# zik-pcb-base-bussed.net
KiCad netlist of a schematic drawn in EAGLE
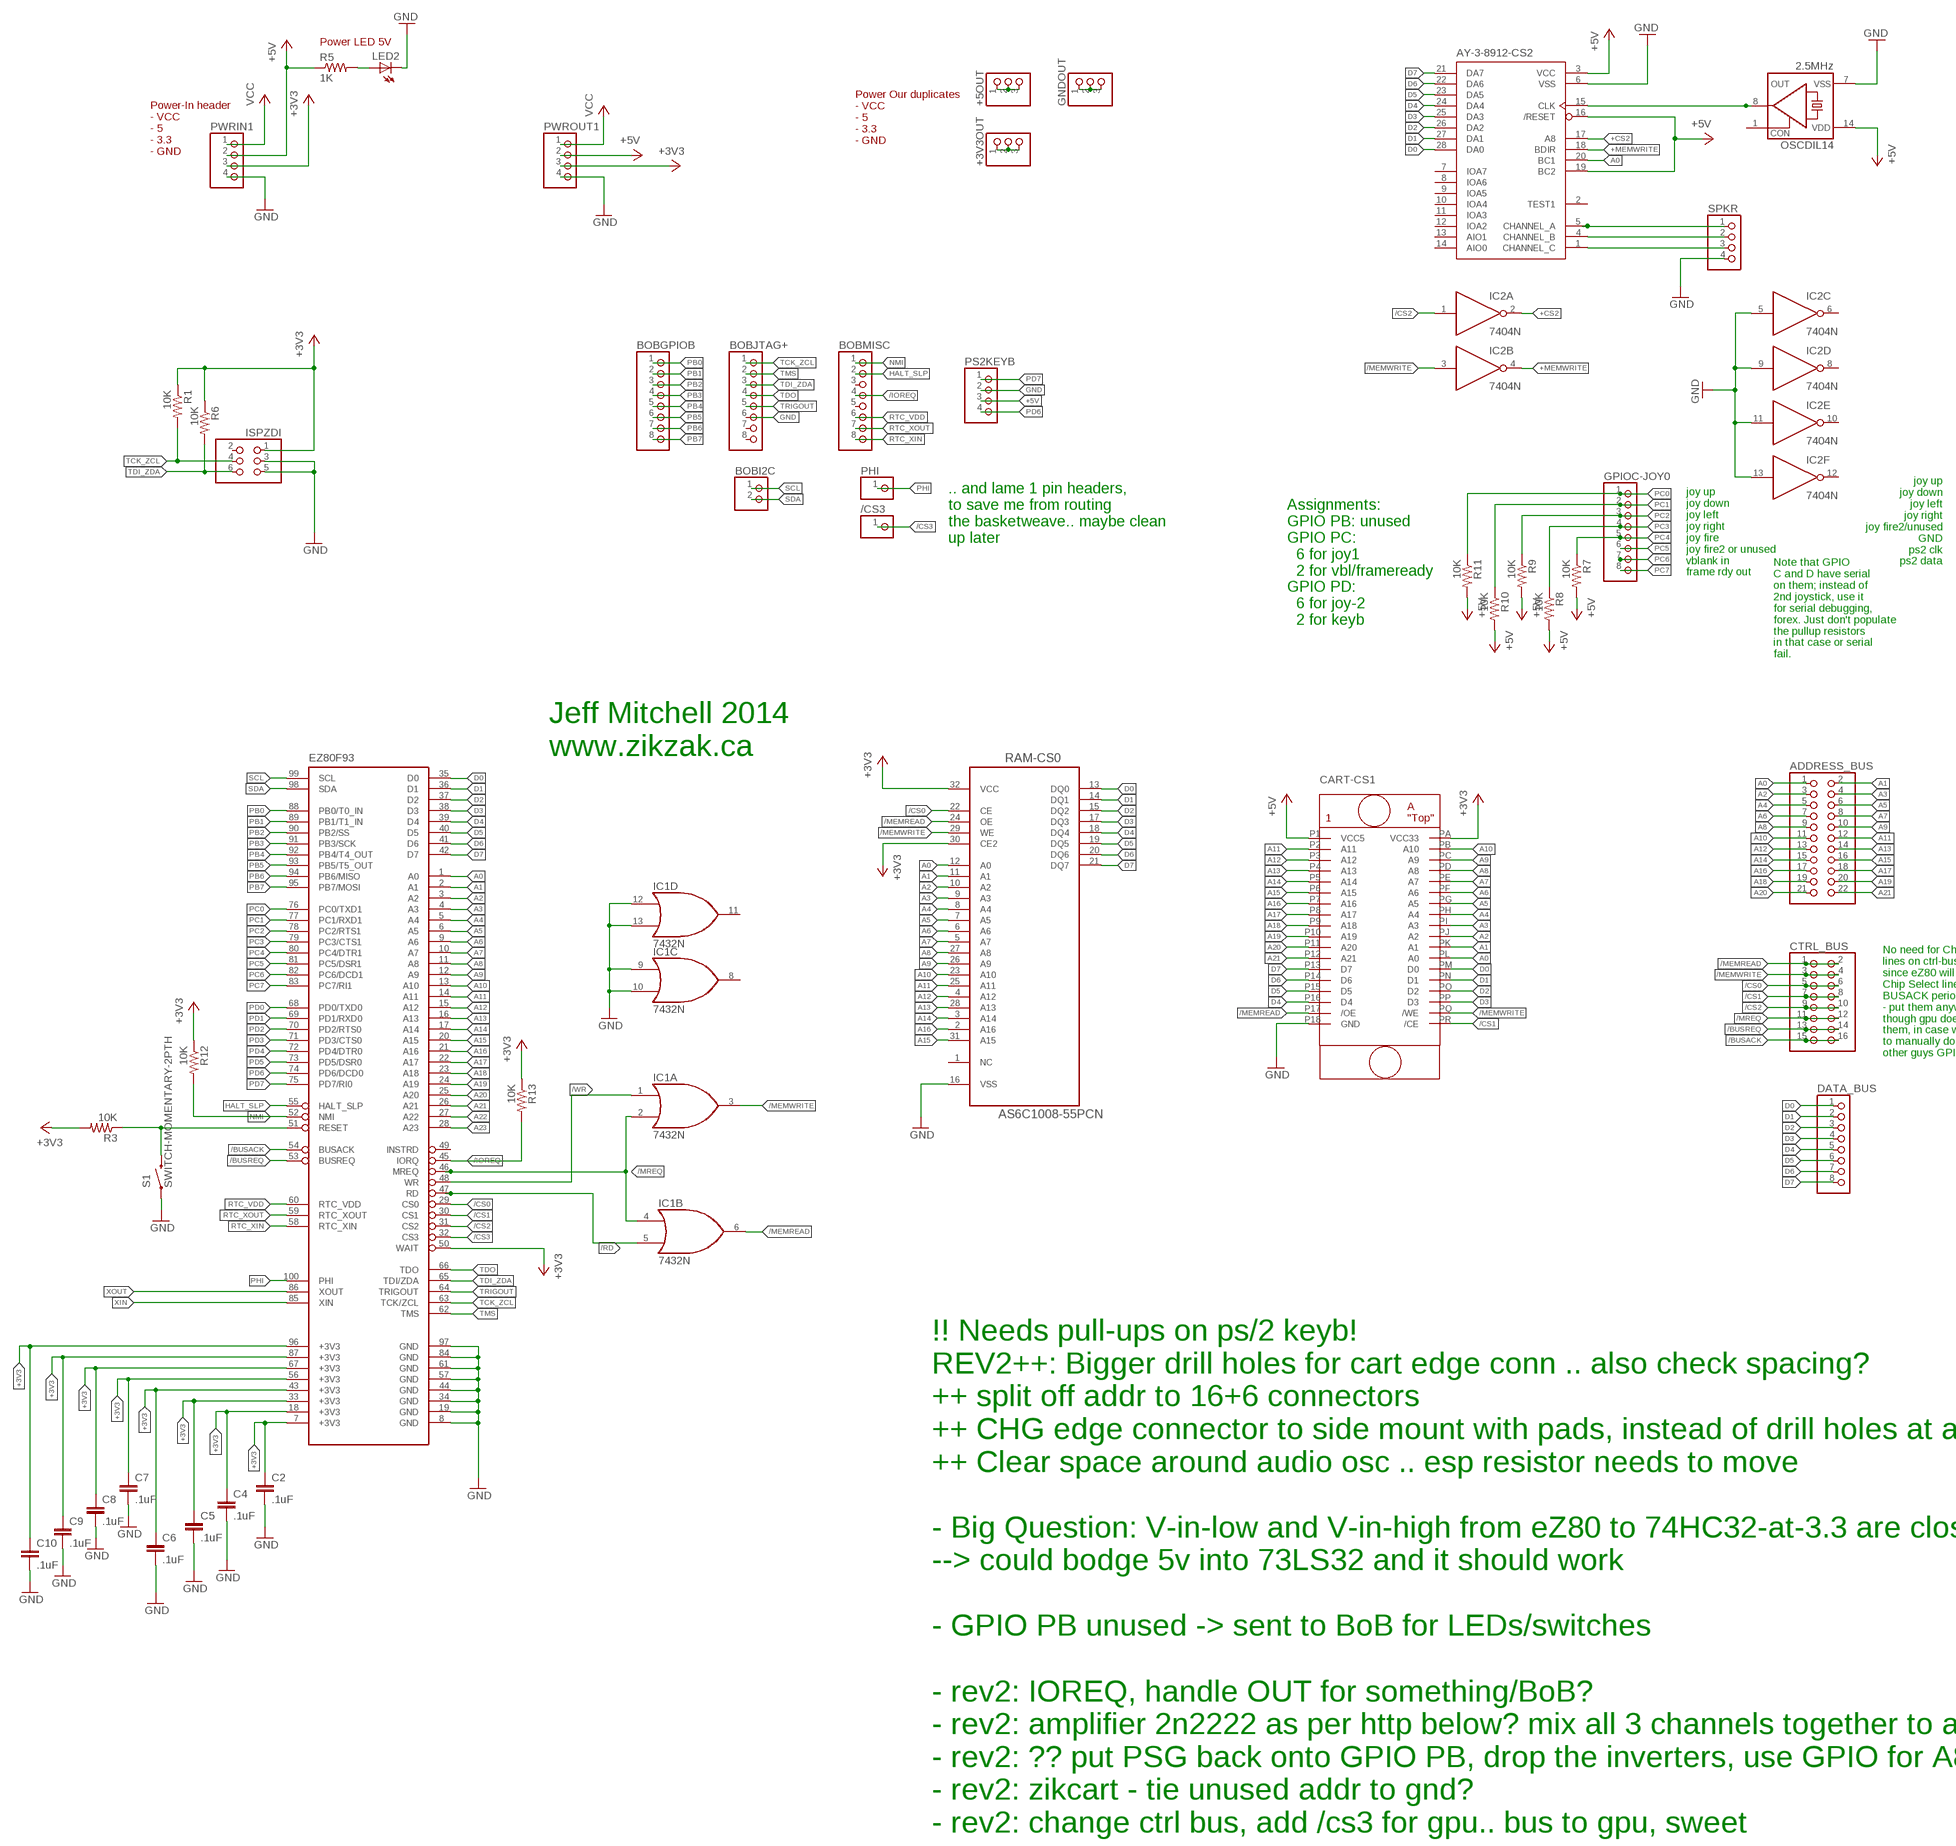
[diagram p0: schematic, sheet 1, part 1 of 2]
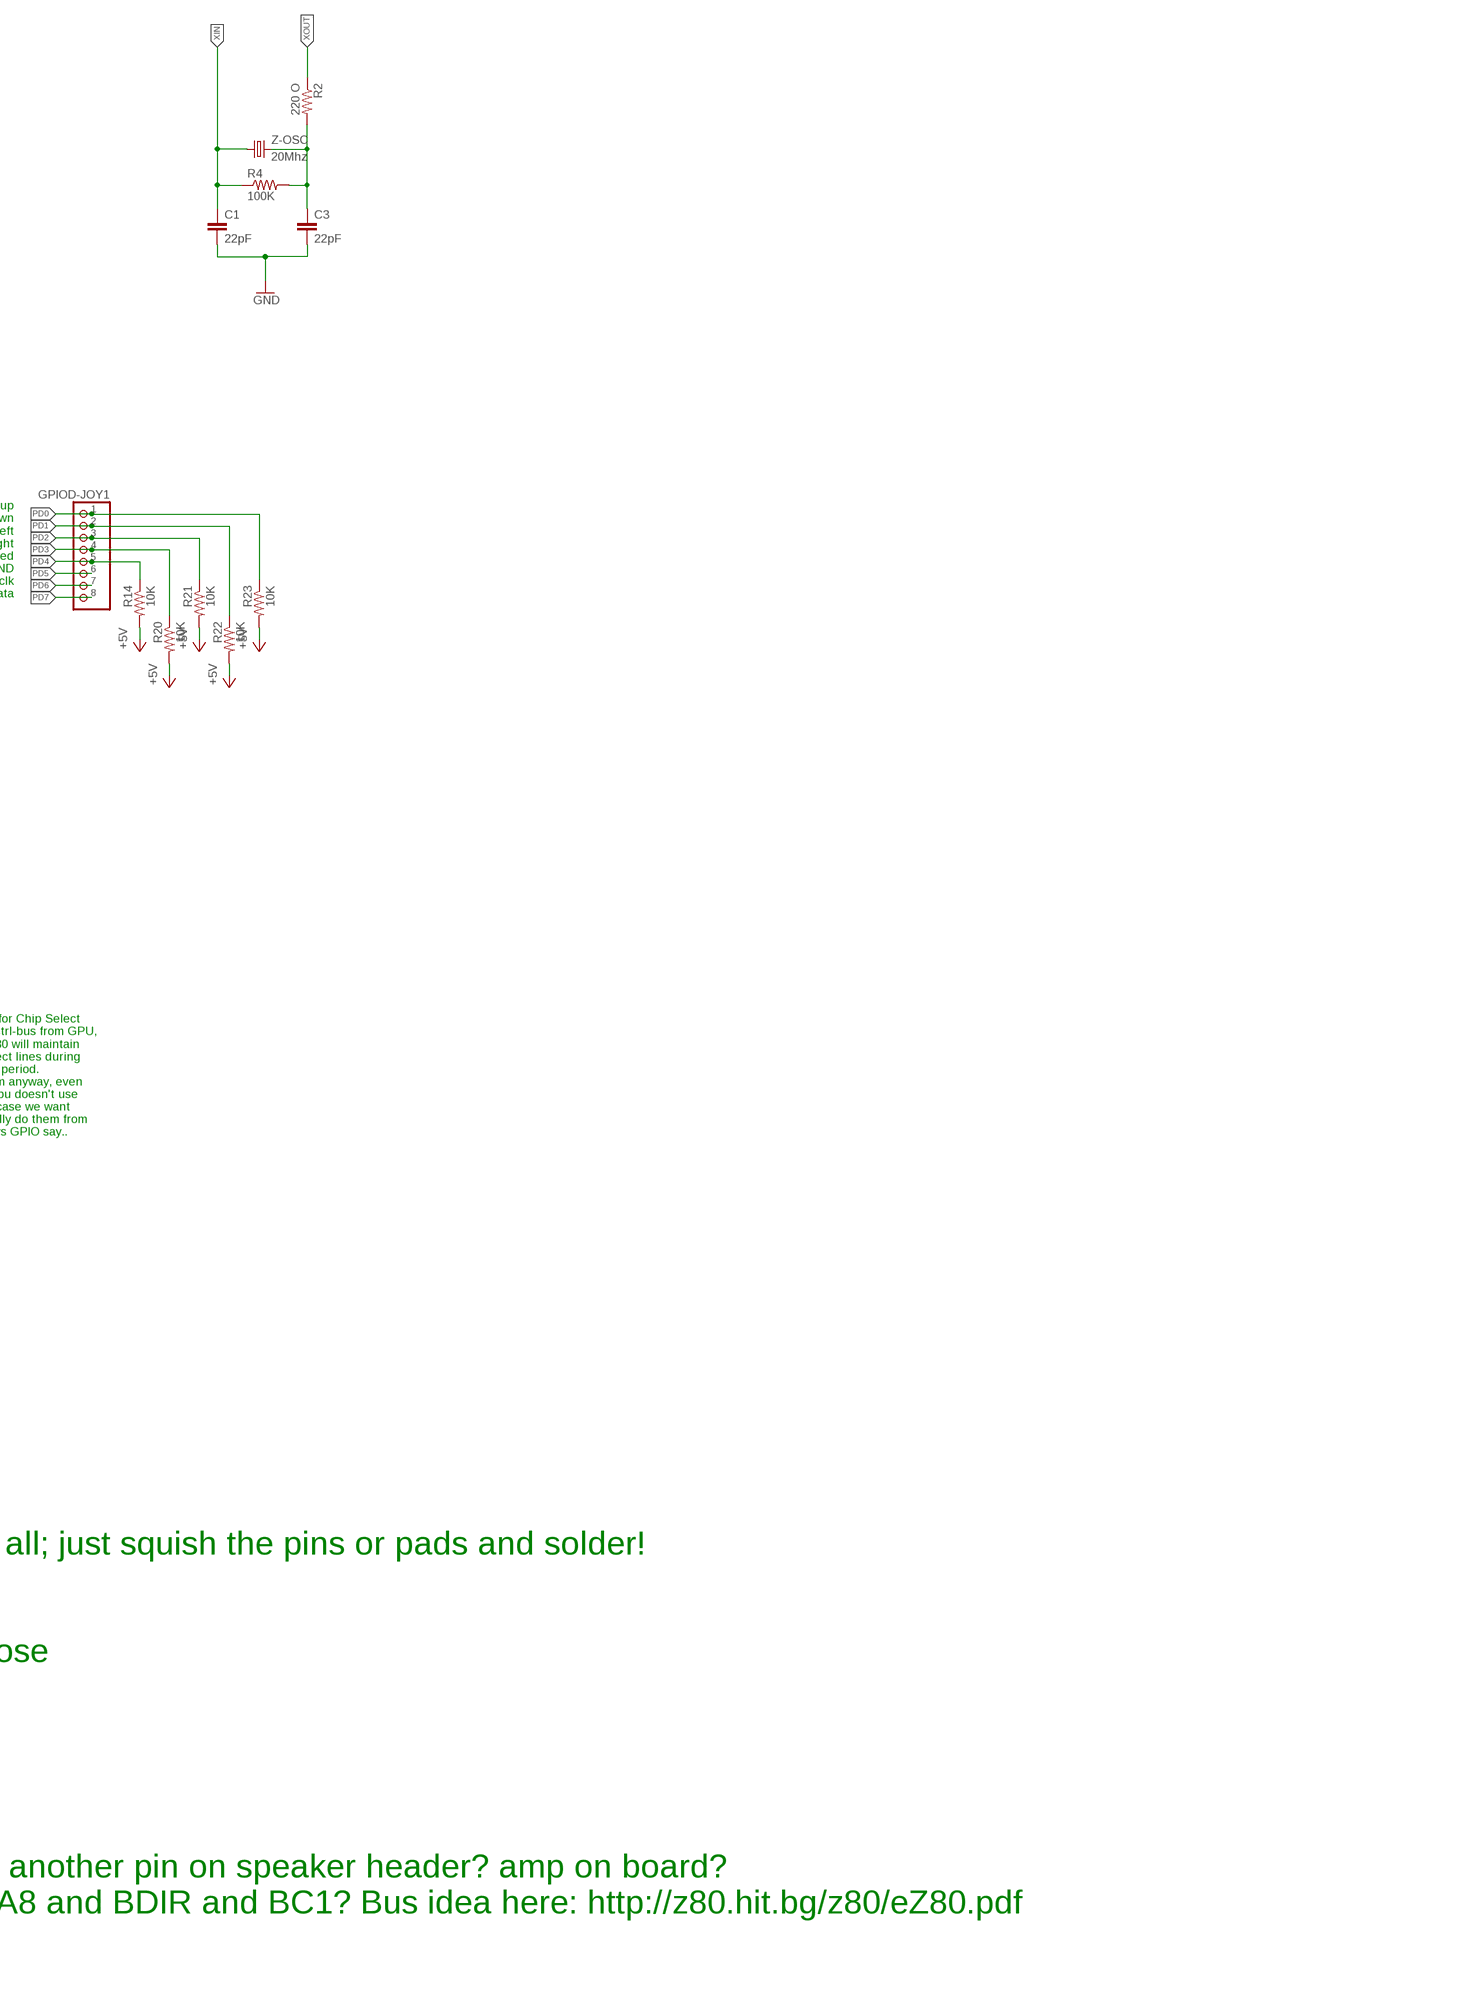
[diagram p1: schematic, sheet 1, part 2 of 2]

(export (version "E")
  (design (tool "Eeschema 10.0.6"))
  (components
    (comp (ref "+3V3OUT")
      (value "PINHD-1X3")
      (footprint "eagle-import:1X03")
      (libsource (lib "eagle-import") (part "PINHD-1X3"))
    )
    (comp (ref "+5OUT")
      (value "PINHD-1X3")
      (footprint "eagle-import:1X03")
      (libsource (lib "eagle-import") (part "PINHD-1X3"))
    )
    (comp (ref "/CS3")
      (value "PINHD-1X1")
      (footprint "eagle-import:1X01")
      (libsource (lib "eagle-import") (part "PINHD-1X1"))
    )
    (comp (ref "ADDRESS_BUS")
      (value "PINHD-2X11")
      (footprint "eagle-import:2X11")
      (libsource (lib "eagle-import") (part "PINHD-2X11"))
    )
    (comp (ref "AY-3-8912-CS2")
      (value "AY-3-8912_28PIN")
      (footprint "eagle-import:DIL28")
      (libsource (lib "eagle-import") (part "AY-3-8912_28PIN"))
    )
    (comp (ref "BOBGPIOB")
      (value "PINHD-1X8")
      (footprint "eagle-import:1X08")
      (libsource (lib "eagle-import") (part "PINHD-1X8"))
    )
    (comp (ref "BOBI2C")
      (value "PINHD-1X2")
      (footprint "eagle-import:1X02")
      (libsource (lib "eagle-import") (part "PINHD-1X2"))
    )
    (comp (ref "BOBJTAG+")
      (value "PINHD-1X8")
      (footprint "eagle-import:1X08")
      (libsource (lib "eagle-import") (part "PINHD-1X8"))
    )
    (comp (ref "BOBMISC")
      (value "PINHD-1X8")
      (footprint "eagle-import:1X08")
      (libsource (lib "eagle-import") (part "PINHD-1X8"))
    )
    (comp (ref "C1")
      (value "22pF")
      (footprint "eagle-import:C025-025X050")
      (libsource (lib "eagle-import") (part "C-EU025-025X050"))
    )
    (comp (ref "C2")
      (value ".1uF")
      (footprint "eagle-import:C025-025X050")
      (libsource (lib "eagle-import") (part "C-EU025-025X050"))
    )
    (comp (ref "C3")
      (value "22pF")
      (footprint "eagle-import:C025-025X050")
      (libsource (lib "eagle-import") (part "C-EU025-025X050"))
    )
    (comp (ref "C4")
      (value ".1uF")
      (footprint "eagle-import:C025-025X050")
      (libsource (lib "eagle-import") (part "C-EU025-025X050"))
    )
    (comp (ref "C5")
      (value ".1uF")
      (footprint "eagle-import:C025-025X050")
      (libsource (lib "eagle-import") (part "C-EU025-025X050"))
    )
    (comp (ref "C6")
      (value ".1uF")
      (footprint "eagle-import:C025-025X050")
      (libsource (lib "eagle-import") (part "C-EU025-025X050"))
    )
    (comp (ref "C7")
      (value ".1uF")
      (footprint "eagle-import:C025-025X050")
      (libsource (lib "eagle-import") (part "C-EU025-025X050"))
    )
    (comp (ref "C8")
      (value ".1uF")
      (footprint "eagle-import:C025-025X050")
      (libsource (lib "eagle-import") (part "C-EU025-025X050"))
    )
    (comp (ref "C9")
      (value ".1uF")
      (footprint "eagle-import:C025-025X050")
      (libsource (lib "eagle-import") (part "C-EU025-025X050"))
    )
    (comp (ref "C10")
      (value ".1uF")
      (footprint "eagle-import:C025-025X050")
      (libsource (lib "eagle-import") (part "C-EU025-025X050"))
    )
    (comp (ref "CART-CS1")
      (value "ZIKCART36")
      (footprint "eagle-import:ZIKCARTSLOT")
      (libsource (lib "eagle-import") (part "ZIKCART36"))
    )
    (comp (ref "CTRL_BUS")
      (value "PINHD-2X8")
      (footprint "eagle-import:2X08")
      (libsource (lib "eagle-import") (part "PINHD-2X8"))
    )
    (comp (ref "DATA_BUS")
      (value "PINHD-1X8")
      (footprint "eagle-import:1X08")
      (libsource (lib "eagle-import") (part "PINHD-1X8"))
    )
    (comp (ref "EZ80F93")
      (value "EZ80F92AZ")
      (footprint "eagle-import:SQFP-S-14X14-100")
      (libsource (lib "eagle-import") (part "EZ80F92AZ"))
    )
    (comp (ref "GNDOUT")
      (value "PINHD-1X3")
      (footprint "eagle-import:1X03")
      (libsource (lib "eagle-import") (part "PINHD-1X3"))
    )
    (comp (ref "GPIOC-JOY0")
      (value "PINHD-1X8")
      (footprint "eagle-import:1X08")
      (libsource (lib "eagle-import") (part "PINHD-1X8"))
    )
    (comp (ref "GPIOD-JOY1")
      (value "PINHD-1X8")
      (footprint "eagle-import:1X08")
      (libsource (lib "eagle-import") (part "PINHD-1X8"))
    )
    (comp (ref "IC1")
      (value "7432N")
      (footprint "eagle-import:DIL14")
      (libsource (lib "eagle-import") (part "7432N"))
    )
    (comp (ref "IC2")
      (value "7404N")
      (footprint "eagle-import:DIL14")
      (libsource (lib "eagle-import") (part "7404N"))
    )
    (comp (ref "ISPZDI")
      (value "PINHD-2X3")
      (footprint "eagle-import:2X03")
      (libsource (lib "eagle-import") (part "PINHD-2X3"))
    )
    (comp (ref "LED2")
      (value "LED5MM")
      (footprint "eagle-import:LED5MM")
      (libsource (lib "eagle-import") (part "LED5MM"))
    )
    (comp (ref "OSCDIL14")
      (value "2.5MHz")
      (footprint "eagle-import:SG51")
      (libsource (lib "eagle-import") (part "CRYSTAL_RES-SG51"))
    )
    (comp (ref "PHI")
      (value "PINHD-1X1")
      (footprint "eagle-import:1X01")
      (libsource (lib "eagle-import") (part "PINHD-1X1"))
    )
    (comp (ref "PS2KEYB")
      (value "PINHD-1X4")
      (footprint "eagle-import:1X04")
      (libsource (lib "eagle-import") (part "PINHD-1X4"))
    )
    (comp (ref "PWRIN1")
      (value "PINHD-1X4")
      (footprint "eagle-import:1X04")
      (libsource (lib "eagle-import") (part "PINHD-1X4"))
    )
    (comp (ref "PWROUT1")
      (value "PINHD-1X4")
      (footprint "eagle-import:1X04")
      (libsource (lib "eagle-import") (part "PINHD-1X4"))
    )
    (comp (ref "R1")
      (value "10K")
      (footprint "eagle-import:0204_7")
      (libsource (lib "eagle-import") (part "R-US_0204/7"))
    )
    (comp (ref "R2")
      (value "220 O")
      (footprint "eagle-import:0204_7")
      (libsource (lib "eagle-import") (part "R-US_0204/7"))
    )
    (comp (ref "R3")
      (value "10K")
      (footprint "eagle-import:0204_7")
      (libsource (lib "eagle-import") (part "R-US_0204/7"))
    )
    (comp (ref "R4")
      (value "100K")
      (footprint "eagle-import:0204_7")
      (libsource (lib "eagle-import") (part "R-US_0204/7"))
    )
    (comp (ref "R5")
      (value "1K")
      (footprint "eagle-import:0207_10")
      (libsource (lib "eagle-import") (part "R-US_0207/10"))
    )
    (comp (ref "R6")
      (value "10K")
      (footprint "eagle-import:0204_7")
      (libsource (lib "eagle-import") (part "R-US_0204/7"))
    )
    (comp (ref "R7")
      (value "10K")
      (footprint "eagle-import:0204_7")
      (libsource (lib "eagle-import") (part "R-US_0204/7"))
    )
    (comp (ref "R8")
      (value "10K")
      (footprint "eagle-import:0204_7")
      (libsource (lib "eagle-import") (part "R-US_0204/7"))
    )
    (comp (ref "R9")
      (value "10K")
      (footprint "eagle-import:0204_7")
      (libsource (lib "eagle-import") (part "R-US_0204/7"))
    )
    (comp (ref "R10")
      (value "10K")
      (footprint "eagle-import:0204_7")
      (libsource (lib "eagle-import") (part "R-US_0204/7"))
    )
    (comp (ref "R11")
      (value "10K")
      (footprint "eagle-import:0204_7")
      (libsource (lib "eagle-import") (part "R-US_0204/7"))
    )
    (comp (ref "R12")
      (value "10K")
      (footprint "eagle-import:0204_7")
      (libsource (lib "eagle-import") (part "R-US_0204/7"))
    )
    (comp (ref "R13")
      (value "10K")
      (footprint "eagle-import:0204_7")
      (libsource (lib "eagle-import") (part "R-US_0204/7"))
    )
    (comp (ref "R14")
      (value "10K")
      (footprint "eagle-import:0204_7")
      (libsource (lib "eagle-import") (part "R-US_0204/7"))
    )
    (comp (ref "R20")
      (value "10K")
      (footprint "eagle-import:0204_7")
      (libsource (lib "eagle-import") (part "R-US_0204/7"))
    )
    (comp (ref "R21")
      (value "10K")
      (footprint "eagle-import:0204_7")
      (libsource (lib "eagle-import") (part "R-US_0204/7"))
    )
    (comp (ref "R22")
      (value "10K")
      (footprint "eagle-import:0204_7")
      (libsource (lib "eagle-import") (part "R-US_0204/7"))
    )
    (comp (ref "R23")
      (value "10K")
      (footprint "eagle-import:0204_7")
      (libsource (lib "eagle-import") (part "R-US_0204/7"))
    )
    (comp (ref "RAM-CS0")
      (value "AS6C1008-55PCN")
      (footprint "eagle-import:DIP254P1524X393-32")
      (libsource (lib "eagle-import") (part "AS6C1008-55PCN"))
    )
    (comp (ref "S1")
      (value "SWITCH-MOMENTARY-2PTH")
      (footprint "eagle-import:TACTILE-PTH")
      (libsource (lib "eagle-import") (part "SWITCH-MOMENTARY-2PTH"))
    )
    (comp (ref "SPKR")
      (value "PINHD-1X4")
      (footprint "eagle-import:1X04")
      (libsource (lib "eagle-import") (part "PINHD-1X4"))
    )
    (comp (ref "Z-OSC")
      (value "20Mhz")
      (footprint "eagle-import:HC49US")
      (libsource (lib "eagle-import") (part "CRYSTALHC49US"))
    )
  )
  (nets
    (net (code "1") (name "+3V3") (class "Default")
      (node (ref "+3V3OUT") (pin "1") (pinfunction "1_1") (pintype "passive"))
      (node (ref "+3V3OUT") (pin "2") (pinfunction "2_2") (pintype "passive"))
      (node (ref "+3V3OUT") (pin "3") (pinfunction "3_3") (pintype "passive"))
      (node (ref "C10") (pin "1") (pinfunction "1_1") (pintype "passive"))
      (node (ref "C2") (pin "1") (pinfunction "1_1") (pintype "passive"))
      (node (ref "C4") (pin "1") (pinfunction "1_1") (pintype "passive"))
      (node (ref "C5") (pin "1") (pinfunction "1_1") (pintype "passive"))
      (node (ref "C6") (pin "1") (pinfunction "1_1") (pintype "passive"))
      (node (ref "C7") (pin "1") (pinfunction "1_1") (pintype "passive"))
      (node (ref "C8") (pin "1") (pinfunction "1_1") (pintype "passive"))
      (node (ref "C9") (pin "1") (pinfunction "1_1") (pintype "passive"))
      (node (ref "CART-CS1") (pin "PA") (pinfunction "VCC33_PA") (pintype "bidirectional"))
      (node (ref "EZ80F93") (pin "18") (pinfunction "+3V3_18") (pintype "power_in"))
      (node (ref "EZ80F93") (pin "33") (pinfunction "+3V3_33") (pintype "power_in"))
      (node (ref "EZ80F93") (pin "43") (pinfunction "+3V3_43") (pintype "power_in"))
      (node (ref "EZ80F93") (pin "50") (pinfunction "WAIT_50") (pintype "input"))
      (node (ref "EZ80F93") (pin "56") (pinfunction "+3V3_56") (pintype "power_in"))
      (node (ref "EZ80F93") (pin "67") (pinfunction "+3V3_67") (pintype "power_in"))
      (node (ref "EZ80F93") (pin "7") (pinfunction "+3V3_7") (pintype "power_in"))
      (node (ref "EZ80F93") (pin "87") (pinfunction "+3V3_87") (pintype "power_in"))
      (node (ref "EZ80F93") (pin "96") (pinfunction "+3V3_96") (pintype "power_in"))
      (node (ref "ISPZDI") (pin "1") (pinfunction "1_1") (pintype "passive"))
      (node (ref "PWRIN1") (pin "3") (pinfunction "3_3") (pintype "passive"))
      (node (ref "PWROUT1") (pin "3") (pinfunction "3_3") (pintype "passive"))
      (node (ref "R1") (pin "1") (pinfunction "1_1") (pintype "passive"))
      (node (ref "R12") (pin "1") (pinfunction "1_1") (pintype "passive"))
      (node (ref "R13") (pin "1") (pinfunction "1_1") (pintype "passive"))
      (node (ref "R3") (pin "2") (pinfunction "2_2") (pintype "passive"))
      (node (ref "R6") (pin "1") (pinfunction "1_1") (pintype "passive"))
      (node (ref "RAM-CS0") (pin "30") (pinfunction "CE2_30") (pintype "input"))
      (node (ref "RAM-CS0") (pin "32") (pinfunction "VCC_32") (pintype "power_in"))
    )
    (net (code "2") (name "+5V") (class "Default")
      (node (ref "+5OUT") (pin "1") (pinfunction "1_1") (pintype "passive"))
      (node (ref "+5OUT") (pin "2") (pinfunction "2_2") (pintype "passive"))
      (node (ref "+5OUT") (pin "3") (pinfunction "3_3") (pintype "passive"))
      (node (ref "AY-3-8912-CS2") (pin "16") (pinfunction "/RESET_16") (pintype "input"))
      (node (ref "AY-3-8912-CS2") (pin "19") (pinfunction "BC2_19") (pintype "input"))
      (node (ref "AY-3-8912-CS2") (pin "3") (pinfunction "VCC_3") (pintype "power_in"))
      (node (ref "CART-CS1") (pin "P1") (pinfunction "VCC5_P1") (pintype "bidirectional"))
      (node (ref "OSCDIL14") (pin "14") (pinfunction "VDD_14") (pintype "power_in"))
      (node (ref "PS2KEYB") (pin "3") (pinfunction "3_3") (pintype "passive"))
      (node (ref "PWRIN1") (pin "2") (pinfunction "2_2") (pintype "passive"))
      (node (ref "PWROUT1") (pin "2") (pinfunction "2_2") (pintype "passive"))
      (node (ref "R10") (pin "2") (pinfunction "2_2") (pintype "passive"))
      (node (ref "R11") (pin "2") (pinfunction "2_2") (pintype "passive"))
      (node (ref "R14") (pin "2") (pinfunction "2_2") (pintype "passive"))
      (node (ref "R20") (pin "2") (pinfunction "2_2") (pintype "passive"))
      (node (ref "R21") (pin "2") (pinfunction "2_2") (pintype "passive"))
      (node (ref "R22") (pin "2") (pinfunction "2_2") (pintype "passive"))
      (node (ref "R23") (pin "2") (pinfunction "2_2") (pintype "passive"))
      (node (ref "R5") (pin "1") (pinfunction "1_1") (pintype "passive"))
      (node (ref "R7") (pin "2") (pinfunction "2_2") (pintype "passive"))
      (node (ref "R8") (pin "2") (pinfunction "2_2") (pintype "passive"))
      (node (ref "R9") (pin "2") (pinfunction "2_2") (pintype "passive"))
    )
    (net (code "3") (name "+CS2") (class "Default")
      (node (ref "AY-3-8912-CS2") (pin "17") (pinfunction "A8_17") (pintype "input"))
      (node (ref "IC2") (pin "2") (pinfunction "O_2") (pintype "output"))
    )
    (net (code "4") (name "+MEMWRITE") (class "Default")
      (node (ref "AY-3-8912-CS2") (pin "18") (pinfunction "BDIR_18") (pintype "input"))
      (node (ref "IC2") (pin "4") (pinfunction "O_4") (pintype "output"))
    )
    (net (code "5") (name "A0") (class "Default")
      (node (ref "ADDRESS_BUS") (pin "1") (pinfunction "1_1") (pintype "passive"))
      (node (ref "AY-3-8912-CS2") (pin "20") (pinfunction "BC1_20") (pintype "input"))
      (node (ref "CART-CS1") (pin "PL") (pinfunction "A0_PL") (pintype "bidirectional"))
      (node (ref "EZ80F93") (pin "1") (pinfunction "A0_1") (pintype "bidirectional"))
      (node (ref "RAM-CS0") (pin "12") (pinfunction "A0_12") (pintype "input"))
    )
    (net (code "6") (name "A1") (class "Default")
      (node (ref "ADDRESS_BUS") (pin "2") (pinfunction "2_2") (pintype "passive"))
      (node (ref "CART-CS1") (pin "PK") (pinfunction "A1_PK") (pintype "bidirectional"))
      (node (ref "EZ80F93") (pin "2") (pinfunction "A1_2") (pintype "bidirectional"))
      (node (ref "RAM-CS0") (pin "11") (pinfunction "A1_11") (pintype "input"))
    )
    (net (code "7") (name "A2") (class "Default")
      (node (ref "ADDRESS_BUS") (pin "3") (pinfunction "3_3") (pintype "passive"))
      (node (ref "CART-CS1") (pin "PJ") (pinfunction "A2_PJ") (pintype "bidirectional"))
      (node (ref "EZ80F93") (pin "3") (pinfunction "A2_3") (pintype "bidirectional"))
      (node (ref "RAM-CS0") (pin "10") (pinfunction "A2_10") (pintype "input"))
    )
    (net (code "8") (name "A3") (class "Default")
      (node (ref "ADDRESS_BUS") (pin "4") (pinfunction "4_4") (pintype "passive"))
      (node (ref "CART-CS1") (pin "PI") (pinfunction "A3_PI") (pintype "bidirectional"))
      (node (ref "EZ80F93") (pin "4") (pinfunction "A3_4") (pintype "bidirectional"))
      (node (ref "RAM-CS0") (pin "9") (pinfunction "A3_9") (pintype "input"))
    )
    (net (code "9") (name "A4") (class "Default")
      (node (ref "ADDRESS_BUS") (pin "5") (pinfunction "5_5") (pintype "passive"))
      (node (ref "CART-CS1") (pin "PH") (pinfunction "A4_PH") (pintype "bidirectional"))
      (node (ref "EZ80F93") (pin "5") (pinfunction "A4_5") (pintype "bidirectional"))
      (node (ref "RAM-CS0") (pin "8") (pinfunction "A4_8") (pintype "input"))
    )
    (net (code "10") (name "A5") (class "Default")
      (node (ref "ADDRESS_BUS") (pin "6") (pinfunction "6_6") (pintype "passive"))
      (node (ref "CART-CS1") (pin "PG") (pinfunction "A5_PG") (pintype "bidirectional"))
      (node (ref "EZ80F93") (pin "6") (pinfunction "A5_6") (pintype "bidirectional"))
      (node (ref "RAM-CS0") (pin "7") (pinfunction "A5_7") (pintype "input"))
    )
    (net (code "11") (name "A6") (class "Default")
      (node (ref "ADDRESS_BUS") (pin "7") (pinfunction "7_7") (pintype "passive"))
      (node (ref "CART-CS1") (pin "PF") (pinfunction "A6_PF") (pintype "bidirectional"))
      (node (ref "EZ80F93") (pin "9") (pinfunction "A6_9") (pintype "bidirectional"))
      (node (ref "RAM-CS0") (pin "6") (pinfunction "A6_6") (pintype "input"))
    )
    (net (code "12") (name "A7") (class "Default")
      (node (ref "ADDRESS_BUS") (pin "8") (pinfunction "8_8") (pintype "passive"))
      (node (ref "CART-CS1") (pin "PE") (pinfunction "A7_PE") (pintype "bidirectional"))
      (node (ref "EZ80F93") (pin "10") (pinfunction "A7_10") (pintype "bidirectional"))
      (node (ref "RAM-CS0") (pin "5") (pinfunction "A7_5") (pintype "input"))
    )
    (net (code "13") (name "A8") (class "Default")
      (node (ref "ADDRESS_BUS") (pin "9") (pinfunction "9_9") (pintype "passive"))
      (node (ref "CART-CS1") (pin "PD") (pinfunction "A8_PD") (pintype "bidirectional"))
      (node (ref "EZ80F93") (pin "11") (pinfunction "A8_11") (pintype "bidirectional"))
      (node (ref "RAM-CS0") (pin "27") (pinfunction "A8_27") (pintype "input"))
    )
    (net (code "14") (name "A9") (class "Default")
      (node (ref "ADDRESS_BUS") (pin "10") (pinfunction "10_10") (pintype "passive"))
      (node (ref "CART-CS1") (pin "PC") (pinfunction "A9_PC") (pintype "bidirectional"))
      (node (ref "EZ80F93") (pin "12") (pinfunction "A9_12") (pintype "bidirectional"))
      (node (ref "RAM-CS0") (pin "26") (pinfunction "A9_26") (pintype "input"))
    )
    (net (code "15") (name "A10") (class "Default")
      (node (ref "ADDRESS_BUS") (pin "11") (pinfunction "11_11") (pintype "passive"))
      (node (ref "CART-CS1") (pin "PB") (pinfunction "A10_PB") (pintype "bidirectional"))
      (node (ref "EZ80F93") (pin "13") (pinfunction "A10_13") (pintype "bidirectional"))
      (node (ref "RAM-CS0") (pin "23") (pinfunction "A10_23") (pintype "input"))
    )
    (net (code "16") (name "A11") (class "Default")
      (node (ref "ADDRESS_BUS") (pin "12") (pinfunction "12_12") (pintype "passive"))
      (node (ref "CART-CS1") (pin "P2") (pinfunction "A11_P2") (pintype "bidirectional"))
      (node (ref "EZ80F93") (pin "14") (pinfunction "A11_14") (pintype "bidirectional"))
      (node (ref "RAM-CS0") (pin "25") (pinfunction "A11_25") (pintype "input"))
    )
    (net (code "17") (name "A12") (class "Default")
      (node (ref "ADDRESS_BUS") (pin "13") (pinfunction "13_13") (pintype "passive"))
      (node (ref "CART-CS1") (pin "P3") (pinfunction "A12_P3") (pintype "bidirectional"))
      (node (ref "EZ80F93") (pin "15") (pinfunction "A12_15") (pintype "bidirectional"))
      (node (ref "RAM-CS0") (pin "4") (pinfunction "A12_4") (pintype "input"))
    )
    (net (code "18") (name "A13") (class "Default")
      (node (ref "ADDRESS_BUS") (pin "14") (pinfunction "14_14") (pintype "passive"))
      (node (ref "CART-CS1") (pin "P4") (pinfunction "A13_P4") (pintype "bidirectional"))
      (node (ref "EZ80F93") (pin "16") (pinfunction "A13_16") (pintype "bidirectional"))
      (node (ref "RAM-CS0") (pin "28") (pinfunction "A13_28") (pintype "input"))
    )
    (net (code "19") (name "A14") (class "Default")
      (node (ref "ADDRESS_BUS") (pin "15") (pinfunction "15_15") (pintype "passive"))
      (node (ref "CART-CS1") (pin "P5") (pinfunction "A14_P5") (pintype "bidirectional"))
      (node (ref "EZ80F93") (pin "17") (pinfunction "A14_17") (pintype "bidirectional"))
      (node (ref "RAM-CS0") (pin "3") (pinfunction "A14_3") (pintype "input"))
    )
    (net (code "20") (name "A15") (class "Default")
      (node (ref "ADDRESS_BUS") (pin "16") (pinfunction "16_16") (pintype "passive"))
      (node (ref "CART-CS1") (pin "P6") (pinfunction "A15_P6") (pintype "bidirectional"))
      (node (ref "EZ80F93") (pin "20") (pinfunction "A15_20") (pintype "bidirectional"))
      (node (ref "RAM-CS0") (pin "31") (pinfunction "A15_31") (pintype "input"))
    )
    (net (code "21") (name "A16") (class "Default")
      (node (ref "ADDRESS_BUS") (pin "17") (pinfunction "17_17") (pintype "passive"))
      (node (ref "CART-CS1") (pin "P7") (pinfunction "A16_P7") (pintype "bidirectional"))
      (node (ref "EZ80F93") (pin "21") (pinfunction "A16_21") (pintype "bidirectional"))
      (node (ref "RAM-CS0") (pin "2") (pinfunction "A16_2") (pintype "input"))
    )
    (net (code "22") (name "A17") (class "Default")
      (node (ref "ADDRESS_BUS") (pin "18") (pinfunction "18_18") (pintype "passive"))
      (node (ref "CART-CS1") (pin "P8") (pinfunction "A17_P8") (pintype "bidirectional"))
      (node (ref "EZ80F93") (pin "22") (pinfunction "A17_22") (pintype "bidirectional"))
    )
    (net (code "23") (name "A18") (class "Default")
      (node (ref "ADDRESS_BUS") (pin "19") (pinfunction "19_19") (pintype "passive"))
      (node (ref "CART-CS1") (pin "P9") (pinfunction "A18_P9") (pintype "bidirectional"))
      (node (ref "EZ80F93") (pin "23") (pinfunction "A18_23") (pintype "bidirectional"))
    )
    (net (code "24") (name "A19") (class "Default")
      (node (ref "ADDRESS_BUS") (pin "20") (pinfunction "20_20") (pintype "passive"))
      (node (ref "CART-CS1") (pin "P10") (pinfunction "A19_P10") (pintype "bidirectional"))
      (node (ref "EZ80F93") (pin "24") (pinfunction "A19_24") (pintype "bidirectional"))
    )
    (net (code "25") (name "A20") (class "Default")
      (node (ref "ADDRESS_BUS") (pin "21") (pinfunction "21_21") (pintype "passive"))
      (node (ref "CART-CS1") (pin "P11") (pinfunction "A20_P11") (pintype "bidirectional"))
      (node (ref "EZ80F93") (pin "25") (pinfunction "A20_25") (pintype "bidirectional"))
    )
    (net (code "26") (name "A21") (class "Default")
      (node (ref "ADDRESS_BUS") (pin "22") (pinfunction "22_22") (pintype "passive"))
      (node (ref "CART-CS1") (pin "P12") (pinfunction "A21_P12") (pintype "bidirectional"))
      (node (ref "EZ80F93") (pin "26") (pinfunction "A21_26") (pintype "bidirectional"))
    )
    (net (code "27") (name "A22") (class "Default")
      (node (ref "EZ80F93") (pin "27") (pinfunction "A22_27") (pintype "bidirectional"))
    )
    (net (code "28") (name "A23") (class "Default")
      (node (ref "EZ80F93") (pin "28") (pinfunction "A23_28") (pintype "bidirectional"))
    )
    (net (code "29") (name "D0") (class "Default")
      (node (ref "AY-3-8912-CS2") (pin "28") (pinfunction "DA0_28") (pintype "bidirectional"))
      (node (ref "CART-CS1") (pin "PM") (pinfunction "D0_PM") (pintype "bidirectional"))
      (node (ref "DATA_BUS") (pin "1") (pinfunction "1_1") (pintype "passive"))
      (node (ref "EZ80F93") (pin "35") (pinfunction "D0_35") (pintype "bidirectional"))
      (node (ref "RAM-CS0") (pin "13") (pinfunction "DQ0_13") (pintype "bidirectional"))
    )
    (net (code "30") (name "D1") (class "Default")
      (node (ref "AY-3-8912-CS2") (pin "27") (pinfunction "DA1_27") (pintype "bidirectional"))
      (node (ref "CART-CS1") (pin "PN") (pinfunction "D1_PN") (pintype "bidirectional"))
      (node (ref "DATA_BUS") (pin "2") (pinfunction "2_2") (pintype "passive"))
      (node (ref "EZ80F93") (pin "36") (pinfunction "D1_36") (pintype "bidirectional"))
      (node (ref "RAM-CS0") (pin "14") (pinfunction "DQ1_14") (pintype "bidirectional"))
    )
    (net (code "31") (name "D2") (class "Default")
      (node (ref "AY-3-8912-CS2") (pin "26") (pinfunction "DA2_26") (pintype "bidirectional"))
      (node (ref "CART-CS1") (pin "PO") (pinfunction "D2_PO") (pintype "bidirectional"))
      (node (ref "DATA_BUS") (pin "3") (pinfunction "3_3") (pintype "passive"))
      (node (ref "EZ80F93") (pin "37") (pinfunction "D2_37") (pintype "bidirectional"))
      (node (ref "RAM-CS0") (pin "15") (pinfunction "DQ2_15") (pintype "bidirectional"))
    )
    (net (code "32") (name "D3") (class "Default")
      (node (ref "AY-3-8912-CS2") (pin "25") (pinfunction "DA3_25") (pintype "bidirectional"))
      (node (ref "CART-CS1") (pin "PP") (pinfunction "D3_PP") (pintype "bidirectional"))
      (node (ref "DATA_BUS") (pin "4") (pinfunction "4_4") (pintype "passive"))
      (node (ref "EZ80F93") (pin "38") (pinfunction "D3_38") (pintype "bidirectional"))
      (node (ref "RAM-CS0") (pin "17") (pinfunction "DQ3_17") (pintype "bidirectional"))
    )
    (net (code "33") (name "D4") (class "Default")
      (node (ref "AY-3-8912-CS2") (pin "24") (pinfunction "DA4_24") (pintype "bidirectional"))
      (node (ref "CART-CS1") (pin "P16") (pinfunction "D4_P16") (pintype "bidirectional"))
      (node (ref "DATA_BUS") (pin "5") (pinfunction "5_5") (pintype "passive"))
      (node (ref "EZ80F93") (pin "39") (pinfunction "D4_39") (pintype "bidirectional"))
      (node (ref "RAM-CS0") (pin "18") (pinfunction "DQ4_18") (pintype "bidirectional"))
    )
    (net (code "34") (name "D5") (class "Default")
      (node (ref "AY-3-8912-CS2") (pin "23") (pinfunction "DA5_23") (pintype "bidirectional"))
      (node (ref "CART-CS1") (pin "P15") (pinfunction "D5_P15") (pintype "bidirectional"))
      (node (ref "DATA_BUS") (pin "6") (pinfunction "6_6") (pintype "passive"))
      (node (ref "EZ80F93") (pin "40") (pinfunction "D5_40") (pintype "bidirectional"))
      (node (ref "RAM-CS0") (pin "19") (pinfunction "DQ5_19") (pintype "bidirectional"))
    )
    (net (code "35") (name "D6") (class "Default")
      (node (ref "AY-3-8912-CS2") (pin "22") (pinfunction "DA6_22") (pintype "bidirectional"))
      (node (ref "CART-CS1") (pin "P14") (pinfunction "D6_P14") (pintype "bidirectional"))
      (node (ref "DATA_BUS") (pin "7") (pinfunction "7_7") (pintype "passive"))
      (node (ref "EZ80F93") (pin "41") (pinfunction "D6_41") (pintype "bidirectional"))
      (node (ref "RAM-CS0") (pin "20") (pinfunction "DQ6_20") (pintype "bidirectional"))
    )
    (net (code "36") (name "D7") (class "Default")
      (node (ref "AY-3-8912-CS2") (pin "21") (pinfunction "DA7_21") (pintype "bidirectional"))
      (node (ref "CART-CS1") (pin "P13") (pinfunction "D7_P13") (pintype "bidirectional"))
      (node (ref "DATA_BUS") (pin "8") (pinfunction "8_8") (pintype "passive"))
      (node (ref "EZ80F93") (pin "42") (pinfunction "D7_42") (pintype "bidirectional"))
      (node (ref "RAM-CS0") (pin "21") (pinfunction "DQ7_21") (pintype "bidirectional"))
    )
    (net (code "37") (name "GND") (class "Default")
      (node (ref "AY-3-8912-CS2") (pin "6") (pinfunction "VSS_6") (pintype "power_in"))
      (node (ref "C1") (pin "2") (pinfunction "2_2") (pintype "passive"))
      (node (ref "C10") (pin "2") (pinfunction "2_2") (pintype "passive"))
      (node (ref "C2") (pin "2") (pinfunction "2_2") (pintype "passive"))
      (node (ref "C3") (pin "2") (pinfunction "2_2") (pintype "passive"))
      (node (ref "C4") (pin "2") (pinfunction "2_2") (pintype "passive"))
      (node (ref "C5") (pin "2") (pinfunction "2_2") (pintype "passive"))
      (node (ref "C6") (pin "2") (pinfunction "2_2") (pintype "passive"))
      (node (ref "C7") (pin "2") (pinfunction "2_2") (pintype "passive"))
      (node (ref "C8") (pin "2") (pinfunction "2_2") (pintype "passive"))
      (node (ref "C9") (pin "2") (pinfunction "2_2") (pintype "passive"))
      (node (ref "CART-CS1") (pin "P18") (pinfunction "GND_P18") (pintype "bidirectional"))
      (node (ref "EZ80F93") (pin "19") (pinfunction "GND_19") (pintype "power_in"))
      (node (ref "EZ80F93") (pin "34") (pinfunction "GND_34") (pintype "power_in"))
      (node (ref "EZ80F93") (pin "44") (pinfunction "GND_44") (pintype "power_in"))
      (node (ref "EZ80F93") (pin "57") (pinfunction "GND_57") (pintype "power_in"))
      (node (ref "EZ80F93") (pin "61") (pinfunction "GND_61") (pintype "power_in"))
      (node (ref "EZ80F93") (pin "8") (pinfunction "GND_8") (pintype "power_in"))
      (node (ref "EZ80F93") (pin "84") (pinfunction "GND_84") (pintype "power_in"))
      (node (ref "EZ80F93") (pin "97") (pinfunction "GND_97") (pintype "power_in"))
      (node (ref "GNDOUT") (pin "1") (pinfunction "1_1") (pintype "passive"))
      (node (ref "GNDOUT") (pin "2") (pinfunction "2_2") (pintype "passive"))
      (node (ref "GNDOUT") (pin "3") (pinfunction "3_3") (pintype "passive"))
      (node (ref "IC1") (pin "10") (pinfunction "I1_10") (pintype "input"))
      (node (ref "IC1") (pin "12") (pinfunction "I0_12") (pintype "input"))
      (node (ref "IC1") (pin "13") (pinfunction "I1_13") (pintype "input"))
      (node (ref "IC1") (pin "9") (pinfunction "I0_9") (pintype "input"))
      (node (ref "IC2") (pin "11") (pinfunction "I_11") (pintype "input"))
      (node (ref "IC2") (pin "13") (pinfunction "I_13") (pintype "input"))
      (node (ref "IC2") (pin "5") (pinfunction "I_5") (pintype "input"))
      (node (ref "IC2") (pin "9") (pinfunction "I_9") (pintype "input"))
      (node (ref "ISPZDI") (pin "3") (pinfunction "3_3") (pintype "passive"))
      (node (ref "ISPZDI") (pin "5") (pinfunction "5_5") (pintype "passive"))
      (node (ref "LED2") (pin "K") (pinfunction "C_K") (pintype "passive"))
      (node (ref "OSCDIL14") (pin "7") (pinfunction "VSS_7") (pintype "power_in"))
      (node (ref "PS2KEYB") (pin "2") (pinfunction "2_2") (pintype "passive"))
      (node (ref "PWRIN1") (pin "4") (pinfunction "4_4") (pintype "passive"))
      (node (ref "PWROUT1") (pin "4") (pinfunction "4_4") (pintype "passive"))
      (node (ref "RAM-CS0") (pin "16") (pinfunction "VSS_16") (pintype "bidirectional"))
      (node (ref "S1") (pin "1") (pinfunction "1_1") (pintype "passive"))
      (node (ref "SPKR") (pin "4") (pinfunction "4_4") (pintype "passive"))
    )
    (net (code "38") (name "HALT_SLP") (class "Default")
      (node (ref "BOBMISC") (pin "2") (pinfunction "2_2") (pintype "passive"))
      (node (ref "EZ80F93") (pin "55") (pinfunction "HALT_SLP_55") (pintype "output"))
    )
    (net (code "39") (name "NMI") (class "Default")
      (node (ref "BOBMISC") (pin "1") (pinfunction "1_1") (pintype "passive"))
      (node (ref "EZ80F93") (pin "52") (pinfunction "NMI_52") (pintype "input"))
      (node (ref "R12") (pin "2") (pinfunction "2_2") (pintype "passive"))
    )
    (net (code "40") (name "Net-(AY-3-8912-CS2-CHANNEL_A)") (class "Default")
      (node (ref "AY-3-8912-CS2") (pin "5") (pinfunction "CHANNEL_A_5") (pintype "output"))
      (node (ref "SPKR") (pin "1") (pinfunction "1_1") (pintype "passive"))
    )
    (net (code "41") (name "Net-(AY-3-8912-CS2-CHANNEL_B)") (class "Default")
      (node (ref "AY-3-8912-CS2") (pin "4") (pinfunction "CHANNEL_B_4") (pintype "output"))
      (node (ref "SPKR") (pin "2") (pinfunction "2_2") (pintype "passive"))
    )
    (net (code "42") (name "Net-(AY-3-8912-CS2-CHANNEL_C)") (class "Default")
      (node (ref "AY-3-8912-CS2") (pin "1") (pinfunction "CHANNEL_C_1") (pintype "output"))
      (node (ref "SPKR") (pin "3") (pinfunction "3_3") (pintype "passive"))
    )
    (net (code "43") (name "Net-(AY-3-8912-CS2-CLK)") (class "Default")
      (node (ref "AY-3-8912-CS2") (pin "15") (pinfunction "CLK_15") (pintype "input"))
      (node (ref "OSCDIL14") (pin "8") (pinfunction "OUT_8") (pintype "output"))
    )
    (net (code "44") (name "Net-(C3-Pad1)") (class "Default")
      (node (ref "C3") (pin "1") (pinfunction "1_1") (pintype "passive"))
      (node (ref "R2") (pin "2") (pinfunction "2_2") (pintype "passive"))
      (node (ref "R4") (pin "2") (pinfunction "2_2") (pintype "passive"))
      (node (ref "Z-OSC") (pin "2") (pinfunction "2_2") (pintype "passive"))
    )
    (net (code "45") (name "Net-(EZ80F93-RESET)") (class "Default")
      (node (ref "EZ80F93") (pin "51") (pinfunction "RESET_51") (pintype "input"))
      (node (ref "R3") (pin "1") (pinfunction "1_1") (pintype "passive"))
      (node (ref "S1") (pin "3") (pinfunction "2_3") (pintype "passive"))
    )
    (net (code "46") (name "Net-(LED2-PadA)") (class "Default")
      (node (ref "LED2") (pin "A") (pinfunction "A_A") (pintype "passive"))
      (node (ref "R5") (pin "2") (pinfunction "2_2") (pintype "passive"))
    )
    (net (code "47") (name "PB0") (class "Default")
      (node (ref "BOBGPIOB") (pin "1") (pinfunction "1_1") (pintype "passive"))
      (node (ref "EZ80F93") (pin "88") (pinfunction "PB0/T0_IN_88") (pintype "bidirectional"))
    )
    (net (code "48") (name "PB1") (class "Default")
      (node (ref "BOBGPIOB") (pin "2") (pinfunction "2_2") (pintype "passive"))
      (node (ref "EZ80F93") (pin "89") (pinfunction "PB1/T1_IN_89") (pintype "bidirectional"))
    )
    (net (code "49") (name "PB2") (class "Default")
      (node (ref "BOBGPIOB") (pin "3") (pinfunction "3_3") (pintype "passive"))
      (node (ref "EZ80F93") (pin "90") (pinfunction "PB2/SS_90") (pintype "bidirectional"))
    )
    (net (code "50") (name "PB3") (class "Default")
      (node (ref "BOBGPIOB") (pin "4") (pinfunction "4_4") (pintype "passive"))
      (node (ref "EZ80F93") (pin "91") (pinfunction "PB3/SCK_91") (pintype "bidirectional"))
    )
    (net (code "51") (name "PB4") (class "Default")
      (node (ref "BOBGPIOB") (pin "5") (pinfunction "5_5") (pintype "passive"))
      (node (ref "EZ80F93") (pin "92") (pinfunction "PB4/T4_OUT_92") (pintype "bidirectional"))
    )
    (net (code "52") (name "PB5") (class "Default")
      (node (ref "BOBGPIOB") (pin "6") (pinfunction "6_6") (pintype "passive"))
      (node (ref "EZ80F93") (pin "93") (pinfunction "PB5/T5_OUT_93") (pintype "bidirectional"))
    )
    (net (code "53") (name "PB6") (class "Default")
      (node (ref "BOBGPIOB") (pin "7") (pinfunction "7_7") (pintype "passive"))
      (node (ref "EZ80F93") (pin "94") (pinfunction "PB6/MISO_94") (pintype "bidirectional"))
    )
    (net (code "54") (name "PB7") (class "Default")
      (node (ref "BOBGPIOB") (pin "8") (pinfunction "8_8") (pintype "passive"))
      (node (ref "EZ80F93") (pin "95") (pinfunction "PB7/MOSI_95") (pintype "bidirectional"))
    )
    (net (code "55") (name "PC0") (class "Default")
      (node (ref "EZ80F93") (pin "76") (pinfunction "PC0/TXD1_76") (pintype "bidirectional"))
      (node (ref "GPIOC-JOY0") (pin "1") (pinfunction "1_1") (pintype "passive"))
      (node (ref "R11") (pin "1") (pinfunction "1_1") (pintype "passive"))
    )
    (net (code "56") (name "PC1") (class "Default")
      (node (ref "EZ80F93") (pin "77") (pinfunction "PC1/RXD1_77") (pintype "bidirectional"))
      (node (ref "GPIOC-JOY0") (pin "2") (pinfunction "2_2") (pintype "passive"))
      (node (ref "R10") (pin "1") (pinfunction "1_1") (pintype "passive"))
    )
    (net (code "57") (name "PC2") (class "Default")
      (node (ref "EZ80F93") (pin "78") (pinfunction "PC2/RTS1_78") (pintype "bidirectional"))
      (node (ref "GPIOC-JOY0") (pin "3") (pinfunction "3_3") (pintype "passive"))
      (node (ref "R9") (pin "1") (pinfunction "1_1") (pintype "passive"))
    )
    (net (code "58") (name "PC3") (class "Default")
      (node (ref "EZ80F93") (pin "79") (pinfunction "PC3/CTS1_79") (pintype "bidirectional"))
      (node (ref "GPIOC-JOY0") (pin "4") (pinfunction "4_4") (pintype "passive"))
      (node (ref "R8") (pin "1") (pinfunction "1_1") (pintype "passive"))
    )
    (net (code "59") (name "PC4") (class "Default")
      (node (ref "EZ80F93") (pin "80") (pinfunction "PC4/DTR1_80") (pintype "bidirectional"))
      (node (ref "GPIOC-JOY0") (pin "5") (pinfunction "5_5") (pintype "passive"))
      (node (ref "R7") (pin "1") (pinfunction "1_1") (pintype "passive"))
    )
    (net (code "60") (name "PC5") (class "Default")
      (node (ref "EZ80F93") (pin "81") (pinfunction "PC5/DSR1_81") (pintype "bidirectional"))
      (node (ref "GPIOC-JOY0") (pin "6") (pinfunction "6_6") (pintype "passive"))
    )
    (net (code "61") (name "PC6") (class "Default")
      (node (ref "EZ80F93") (pin "82") (pinfunction "PC6/DCD1_82") (pintype "bidirectional"))
      (node (ref "GPIOC-JOY0") (pin "7") (pinfunction "7_7") (pintype "passive"))
    )
    (net (code "62") (name "PC7") (class "Default")
      (node (ref "EZ80F93") (pin "83") (pinfunction "PC7/RI1_83") (pintype "bidirectional"))
      (node (ref "GPIOC-JOY0") (pin "8") (pinfunction "8_8") (pintype "passive"))
    )
    (net (code "63") (name "PD0") (class "Default")
      (node (ref "EZ80F93") (pin "68") (pinfunction "PD0/TXD0_68") (pintype "bidirectional"))
      (node (ref "GPIOD-JOY1") (pin "1") (pinfunction "1_1") (pintype "passive"))
      (node (ref "R23") (pin "1") (pinfunction "1_1") (pintype "passive"))
    )
    (net (code "64") (name "PD1") (class "Default")
      (node (ref "EZ80F93") (pin "69") (pinfunction "PD1/RXD0_69") (pintype "bidirectional"))
      (node (ref "GPIOD-JOY1") (pin "2") (pinfunction "2_2") (pintype "passive"))
      (node (ref "R22") (pin "1") (pinfunction "1_1") (pintype "passive"))
    )
    (net (code "65") (name "PD2") (class "Default")
      (node (ref "EZ80F93") (pin "70") (pinfunction "PD2/RTS0_70") (pintype "bidirectional"))
      (node (ref "GPIOD-JOY1") (pin "3") (pinfunction "3_3") (pintype "passive"))
      (node (ref "R21") (pin "1") (pinfunction "1_1") (pintype "passive"))
    )
    (net (code "66") (name "PD3") (class "Default")
      (node (ref "EZ80F93") (pin "71") (pinfunction "PD3/CTS0_71") (pintype "bidirectional"))
      (node (ref "GPIOD-JOY1") (pin "4") (pinfunction "4_4") (pintype "passive"))
      (node (ref "R20") (pin "1") (pinfunction "1_1") (pintype "passive"))
    )
    (net (code "67") (name "PD4") (class "Default")
      (node (ref "EZ80F93") (pin "72") (pinfunction "PD4/DTR0_72") (pintype "bidirectional"))
      (node (ref "GPIOD-JOY1") (pin "5") (pinfunction "5_5") (pintype "passive"))
      (node (ref "R14") (pin "1") (pinfunction "1_1") (pintype "passive"))
    )
    (net (code "68") (name "PD5") (class "Default")
      (node (ref "EZ80F93") (pin "73") (pinfunction "PD5/DSR0_73") (pintype "bidirectional"))
      (node (ref "GPIOD-JOY1") (pin "6") (pinfunction "6_6") (pintype "passive"))
    )
    (net (code "69") (name "PD6") (class "Default")
      (node (ref "EZ80F93") (pin "74") (pinfunction "PD6/DCD0_74") (pintype "bidirectional"))
      (node (ref "GPIOD-JOY1") (pin "7") (pinfunction "7_7") (pintype "passive"))
      (node (ref "PS2KEYB") (pin "4") (pinfunction "4_4") (pintype "passive"))
    )
    (net (code "70") (name "PD7") (class "Default")
      (node (ref "EZ80F93") (pin "75") (pinfunction "PD7/RI0_75") (pintype "bidirectional"))
      (node (ref "GPIOD-JOY1") (pin "8") (pinfunction "8_8") (pintype "passive"))
      (node (ref "PS2KEYB") (pin "1") (pinfunction "1_1") (pintype "passive"))
    )
    (net (code "71") (name "PHI") (class "Default")
      (node (ref "EZ80F93") (pin "100") (pinfunction "PHI_100") (pintype "output"))
      (node (ref "PHI") (pin "1") (pinfunction "1_1") (pintype "passive"))
    )
    (net (code "72") (name "RTC_VDD") (class "Default")
      (node (ref "BOBMISC") (pin "6") (pinfunction "6_6") (pintype "passive"))
      (node (ref "EZ80F93") (pin "60") (pinfunction "RTC_VDD_60") (pintype "power_in"))
    )
    (net (code "73") (name "RTC_XIN") (class "Default")
      (node (ref "BOBMISC") (pin "8") (pinfunction "8_8") (pintype "passive"))
      (node (ref "EZ80F93") (pin "58") (pinfunction "RTC_XIN_58") (pintype "input"))
    )
    (net (code "74") (name "RTC_XOUT") (class "Default")
      (node (ref "BOBMISC") (pin "7") (pinfunction "7_7") (pintype "passive"))
      (node (ref "EZ80F93") (pin "59") (pinfunction "RTC_XOUT_59") (pintype "bidirectional"))
    )
    (net (code "75") (name "SCL") (class "Default")
      (node (ref "BOBI2C") (pin "1") (pinfunction "1_1") (pintype "passive"))
      (node (ref "EZ80F93") (pin "99") (pinfunction "SCL_99") (pintype "bidirectional"))
    )
    (net (code "76") (name "SDA") (class "Default")
      (node (ref "BOBI2C") (pin "2") (pinfunction "2_2") (pintype "passive"))
      (node (ref "EZ80F93") (pin "98") (pinfunction "SDA_98") (pintype "bidirectional"))
    )
    (net (code "77") (name "TCK_ZCL") (class "Default")
      (node (ref "BOBJTAG+") (pin "1") (pinfunction "1_1") (pintype "passive"))
      (node (ref "EZ80F93") (pin "63") (pinfunction "TCK/ZCL_63") (pintype "input"))
      (node (ref "ISPZDI") (pin "4") (pinfunction "4_4") (pintype "passive"))
      (node (ref "R1") (pin "2") (pinfunction "2_2") (pintype "passive"))
    )
    (net (code "78") (name "TDI_ZDA") (class "Default")
      (node (ref "BOBJTAG+") (pin "3") (pinfunction "3_3") (pintype "passive"))
      (node (ref "EZ80F93") (pin "65") (pinfunction "TDI/ZDA_65") (pintype "bidirectional"))
      (node (ref "ISPZDI") (pin "6") (pinfunction "6_6") (pintype "passive"))
      (node (ref "R6") (pin "2") (pinfunction "2_2") (pintype "passive"))
    )
    (net (code "79") (name "TDO") (class "Default")
      (node (ref "BOBJTAG+") (pin "4") (pinfunction "4_4") (pintype "passive"))
      (node (ref "EZ80F93") (pin "66") (pinfunction "TDO_66") (pintype "output"))
    )
    (net (code "80") (name "TMS") (class "Default")
      (node (ref "BOBJTAG+") (pin "2") (pinfunction "2_2") (pintype "passive"))
      (node (ref "EZ80F93") (pin "62") (pinfunction "TMS_62") (pintype "input"))
    )
    (net (code "81") (name "TRIGOUT") (class "Default")
      (node (ref "BOBJTAG+") (pin "5") (pinfunction "5_5") (pintype "passive"))
      (node (ref "EZ80F93") (pin "64") (pinfunction "TRIGOUT_64") (pintype "output"))
    )
    (net (code "82") (name "VCC") (class "Default")
      (node (ref "PWRIN1") (pin "1") (pinfunction "1_1") (pintype "passive"))
      (node (ref "PWROUT1") (pin "1") (pinfunction "1_1") (pintype "passive"))
    )
    (net (code "83") (name "XIN") (class "Default")
      (node (ref "C1") (pin "1") (pinfunction "1_1") (pintype "passive"))
      (node (ref "EZ80F93") (pin "85") (pinfunction "XIN_85") (pintype "input"))
      (node (ref "R4") (pin "1") (pinfunction "1_1") (pintype "passive"))
      (node (ref "Z-OSC") (pin "1") (pinfunction "1_1") (pintype "passive"))
    )
    (net (code "84") (name "XOUT") (class "Default")
      (node (ref "EZ80F93") (pin "86") (pinfunction "XOUT_86") (pintype "output"))
      (node (ref "R2") (pin "1") (pinfunction "1_1") (pintype "passive"))
    )
    (net (code "85") (name "unconnected-(AY-3-8912-CS2-AIO0-Pad14)") (class "Default")
      (node (ref "AY-3-8912-CS2") (pin "14") (pinfunction "AIO0_14") (pintype "bidirectional"))
    )
    (net (code "86") (name "unconnected-(AY-3-8912-CS2-AIO1-Pad13)") (class "Default")
      (node (ref "AY-3-8912-CS2") (pin "13") (pinfunction "AIO1_13") (pintype "bidirectional"))
    )
    (net (code "87") (name "unconnected-(AY-3-8912-CS2-IOA2-Pad12)") (class "Default")
      (node (ref "AY-3-8912-CS2") (pin "12") (pinfunction "IOA2_12") (pintype "bidirectional"))
    )
    (net (code "88") (name "unconnected-(AY-3-8912-CS2-IOA3-Pad11)") (class "Default")
      (node (ref "AY-3-8912-CS2") (pin "11") (pinfunction "IOA3_11") (pintype "bidirectional"))
    )
    (net (code "89") (name "unconnected-(AY-3-8912-CS2-IOA4-Pad10)") (class "Default")
      (node (ref "AY-3-8912-CS2") (pin "10") (pinfunction "IOA4_10") (pintype "bidirectional"))
    )
    (net (code "90") (name "unconnected-(AY-3-8912-CS2-IOA5-Pad9)") (class "Default")
      (node (ref "AY-3-8912-CS2") (pin "9") (pinfunction "IOA5_9") (pintype "bidirectional"))
    )
    (net (code "91") (name "unconnected-(AY-3-8912-CS2-IOA6-Pad8)") (class "Default")
      (node (ref "AY-3-8912-CS2") (pin "8") (pinfunction "IOA6_8") (pintype "bidirectional"))
    )
    (net (code "92") (name "unconnected-(AY-3-8912-CS2-IOA7-Pad7)") (class "Default")
      (node (ref "AY-3-8912-CS2") (pin "7") (pinfunction "IOA7_7") (pintype "bidirectional"))
    )
    (net (code "93") (name "unconnected-(AY-3-8912-CS2-TEST1-Pad2)") (class "Default")
      (node (ref "AY-3-8912-CS2") (pin "2") (pinfunction "TEST1_2") (pintype "no_connect"))
    )
    (net (code "94") (name "unconnected-(BOBJTAG+-Pad6)") (class "Default")
      (node (ref "BOBJTAG+") (pin "6") (pinfunction "6_6") (pintype "passive"))
    )
    (net (code "95") (name "unconnected-(BOBJTAG+-Pad7)") (class "Default")
      (node (ref "BOBJTAG+") (pin "7") (pinfunction "7_7") (pintype "passive"))
    )
    (net (code "96") (name "unconnected-(BOBJTAG+-Pad8)") (class "Default")
      (node (ref "BOBJTAG+") (pin "8") (pinfunction "8_8") (pintype "passive"))
    )
    (net (code "97") (name "unconnected-(BOBMISC-Pad3)") (class "Default")
      (node (ref "BOBMISC") (pin "3") (pinfunction "3_3") (pintype "passive"))
    )
    (net (code "98") (name "unconnected-(BOBMISC-Pad5)") (class "Default")
      (node (ref "BOBMISC") (pin "5") (pinfunction "5_5") (pintype "passive"))
    )
    (net (code "99") (name "unconnected-(EZ80F93-INSTRD-Pad49)") (class "Default")
      (node (ref "EZ80F93") (pin "49") (pinfunction "INSTRD_49") (pintype "output"))
    )
    (net (code "100") (name "unconnected-(IC1C-O-Pad8)") (class "Default")
      (node (ref "IC1") (pin "8") (pinfunction "O_8") (pintype "output"))
    )
    (net (code "101") (name "unconnected-(IC1D-O-Pad11)") (class "Default")
      (node (ref "IC1") (pin "11") (pinfunction "O_11") (pintype "output"))
    )
    (net (code "102") (name "unconnected-(IC2C-O-Pad6)") (class "Default")
      (node (ref "IC2") (pin "6") (pinfunction "O_6") (pintype "output"))
    )
    (net (code "103") (name "unconnected-(IC2D-O-Pad8)") (class "Default")
      (node (ref "IC2") (pin "8") (pinfunction "O_8") (pintype "output"))
    )
    (net (code "104") (name "unconnected-(IC2E-O-Pad10)") (class "Default")
      (node (ref "IC2") (pin "10") (pinfunction "O_10") (pintype "output"))
    )
    (net (code "105") (name "unconnected-(IC2F-O-Pad12)") (class "Default")
      (node (ref "IC2") (pin "12") (pinfunction "O_12") (pintype "output"))
    )
    (net (code "106") (name "unconnected-(ISPZDI-Pad2)") (class "Default")
      (node (ref "ISPZDI") (pin "2") (pinfunction "2_2") (pintype "passive"))
    )
    (net (code "107") (name "unconnected-(OSCDIL14-CON-Pad1)") (class "Default")
      (node (ref "OSCDIL14") (pin "1") (pinfunction "CON_1") (pintype "input"))
    )
    (net (code "108") (name "unconnected-(RAM-CS0-NC-Pad1)") (class "Default")
      (node (ref "RAM-CS0") (pin "1") (pinfunction "NC_1") (pintype "no_connect"))
    )
    (net (code "109") (name "{slash}BUSACK") (class "Default")
      (node (ref "CTRL_BUS") (pin "15") (pinfunction "15_15") (pintype "passive"))
      (node (ref "CTRL_BUS") (pin "16") (pinfunction "16_16") (pintype "passive"))
      (node (ref "EZ80F93") (pin "54") (pinfunction "BUSACK_54") (pintype "output"))
    )
    (net (code "110") (name "{slash}BUSREQ") (class "Default")
      (node (ref "CTRL_BUS") (pin "13") (pinfunction "13_13") (pintype "passive"))
      (node (ref "CTRL_BUS") (pin "14") (pinfunction "14_14") (pintype "passive"))
      (node (ref "EZ80F93") (pin "53") (pinfunction "BUSREQ_53") (pintype "input"))
    )
    (net (code "111") (name "{slash}CS0") (class "Default")
      (node (ref "CTRL_BUS") (pin "5") (pinfunction "5_5") (pintype "passive"))
      (node (ref "CTRL_BUS") (pin "6") (pinfunction "6_6") (pintype "passive"))
      (node (ref "EZ80F93") (pin "29") (pinfunction "CS0_29") (pintype "output"))
      (node (ref "RAM-CS0") (pin "22") (pinfunction "CE_22") (pintype "input"))
    )
    (net (code "112") (name "{slash}CS1") (class "Default")
      (node (ref "CART-CS1") (pin "PR") (pinfunction "/CE_PR") (pintype "bidirectional"))
      (node (ref "CTRL_BUS") (pin "7") (pinfunction "7_7") (pintype "passive"))
      (node (ref "CTRL_BUS") (pin "8") (pinfunction "8_8") (pintype "passive"))
      (node (ref "EZ80F93") (pin "30") (pinfunction "CS1_30") (pintype "output"))
    )
    (net (code "113") (name "{slash}CS2") (class "Default")
      (node (ref "CTRL_BUS") (pin "10") (pinfunction "10_10") (pintype "passive"))
      (node (ref "CTRL_BUS") (pin "9") (pinfunction "9_9") (pintype "passive"))
      (node (ref "EZ80F93") (pin "31") (pinfunction "CS2_31") (pintype "output"))
      (node (ref "IC2") (pin "1") (pinfunction "I_1") (pintype "input"))
    )
    (net (code "114") (name "{slash}CS3") (class "Default")
      (node (ref "/CS3") (pin "1") (pinfunction "1_1") (pintype "passive"))
      (node (ref "EZ80F93") (pin "32") (pinfunction "CS3_32") (pintype "output"))
    )
    (net (code "115") (name "{slash}IOREQ") (class "Default")
      (node (ref "BOBMISC") (pin "4") (pinfunction "4_4") (pintype "passive"))
      (node (ref "EZ80F93") (pin "45") (pinfunction "IORQ_45") (pintype "bidirectional"))
      (node (ref "R13") (pin "2") (pinfunction "2_2") (pintype "passive"))
    )
    (net (code "116") (name "{slash}MEMREAD") (class "Default")
      (node (ref "CART-CS1") (pin "P17") (pinfunction "/OE_P17") (pintype "bidirectional"))
      (node (ref "CTRL_BUS") (pin "1") (pinfunction "1_1") (pintype "passive"))
      (node (ref "CTRL_BUS") (pin "2") (pinfunction "2_2") (pintype "passive"))
      (node (ref "IC1") (pin "6") (pinfunction "O_6") (pintype "output"))
      (node (ref "RAM-CS0") (pin "24") (pinfunction "OE_24") (pintype "input"))
    )
    (net (code "117") (name "{slash}MEMWRITE") (class "Default")
      (node (ref "CART-CS1") (pin "PQ") (pinfunction "/WE_PQ") (pintype "bidirectional"))
      (node (ref "CTRL_BUS") (pin "3") (pinfunction "3_3") (pintype "passive"))
      (node (ref "CTRL_BUS") (pin "4") (pinfunction "4_4") (pintype "passive"))
      (node (ref "IC1") (pin "3") (pinfunction "O_3") (pintype "output"))
      (node (ref "IC2") (pin "3") (pinfunction "I_3") (pintype "input"))
      (node (ref "RAM-CS0") (pin "29") (pinfunction "WE_29") (pintype "input"))
    )
    (net (code "118") (name "{slash}MREQ") (class "Default")
      (node (ref "CTRL_BUS") (pin "11") (pinfunction "11_11") (pintype "passive"))
      (node (ref "CTRL_BUS") (pin "12") (pinfunction "12_12") (pintype "passive"))
      (node (ref "EZ80F93") (pin "46") (pinfunction "MREQ_46") (pintype "bidirectional"))
      (node (ref "IC1") (pin "2") (pinfunction "I1_2") (pintype "input"))
      (node (ref "IC1") (pin "4") (pinfunction "I0_4") (pintype "input"))
    )
    (net (code "119") (name "{slash}RD") (class "Default")
      (node (ref "EZ80F93") (pin "47") (pinfunction "RD_47") (pintype "output"))
      (node (ref "IC1") (pin "5") (pinfunction "I1_5") (pintype "input"))
    )
    (net (code "120") (name "{slash}WR") (class "Default")
      (node (ref "EZ80F93") (pin "48") (pinfunction "WR_48") (pintype "output"))
      (node (ref "IC1") (pin "1") (pinfunction "I0_1") (pintype "input"))
    )
  )
)
